# 06cpu_soc.net
KiCad netlist of a schematic drawn in Altium Designer
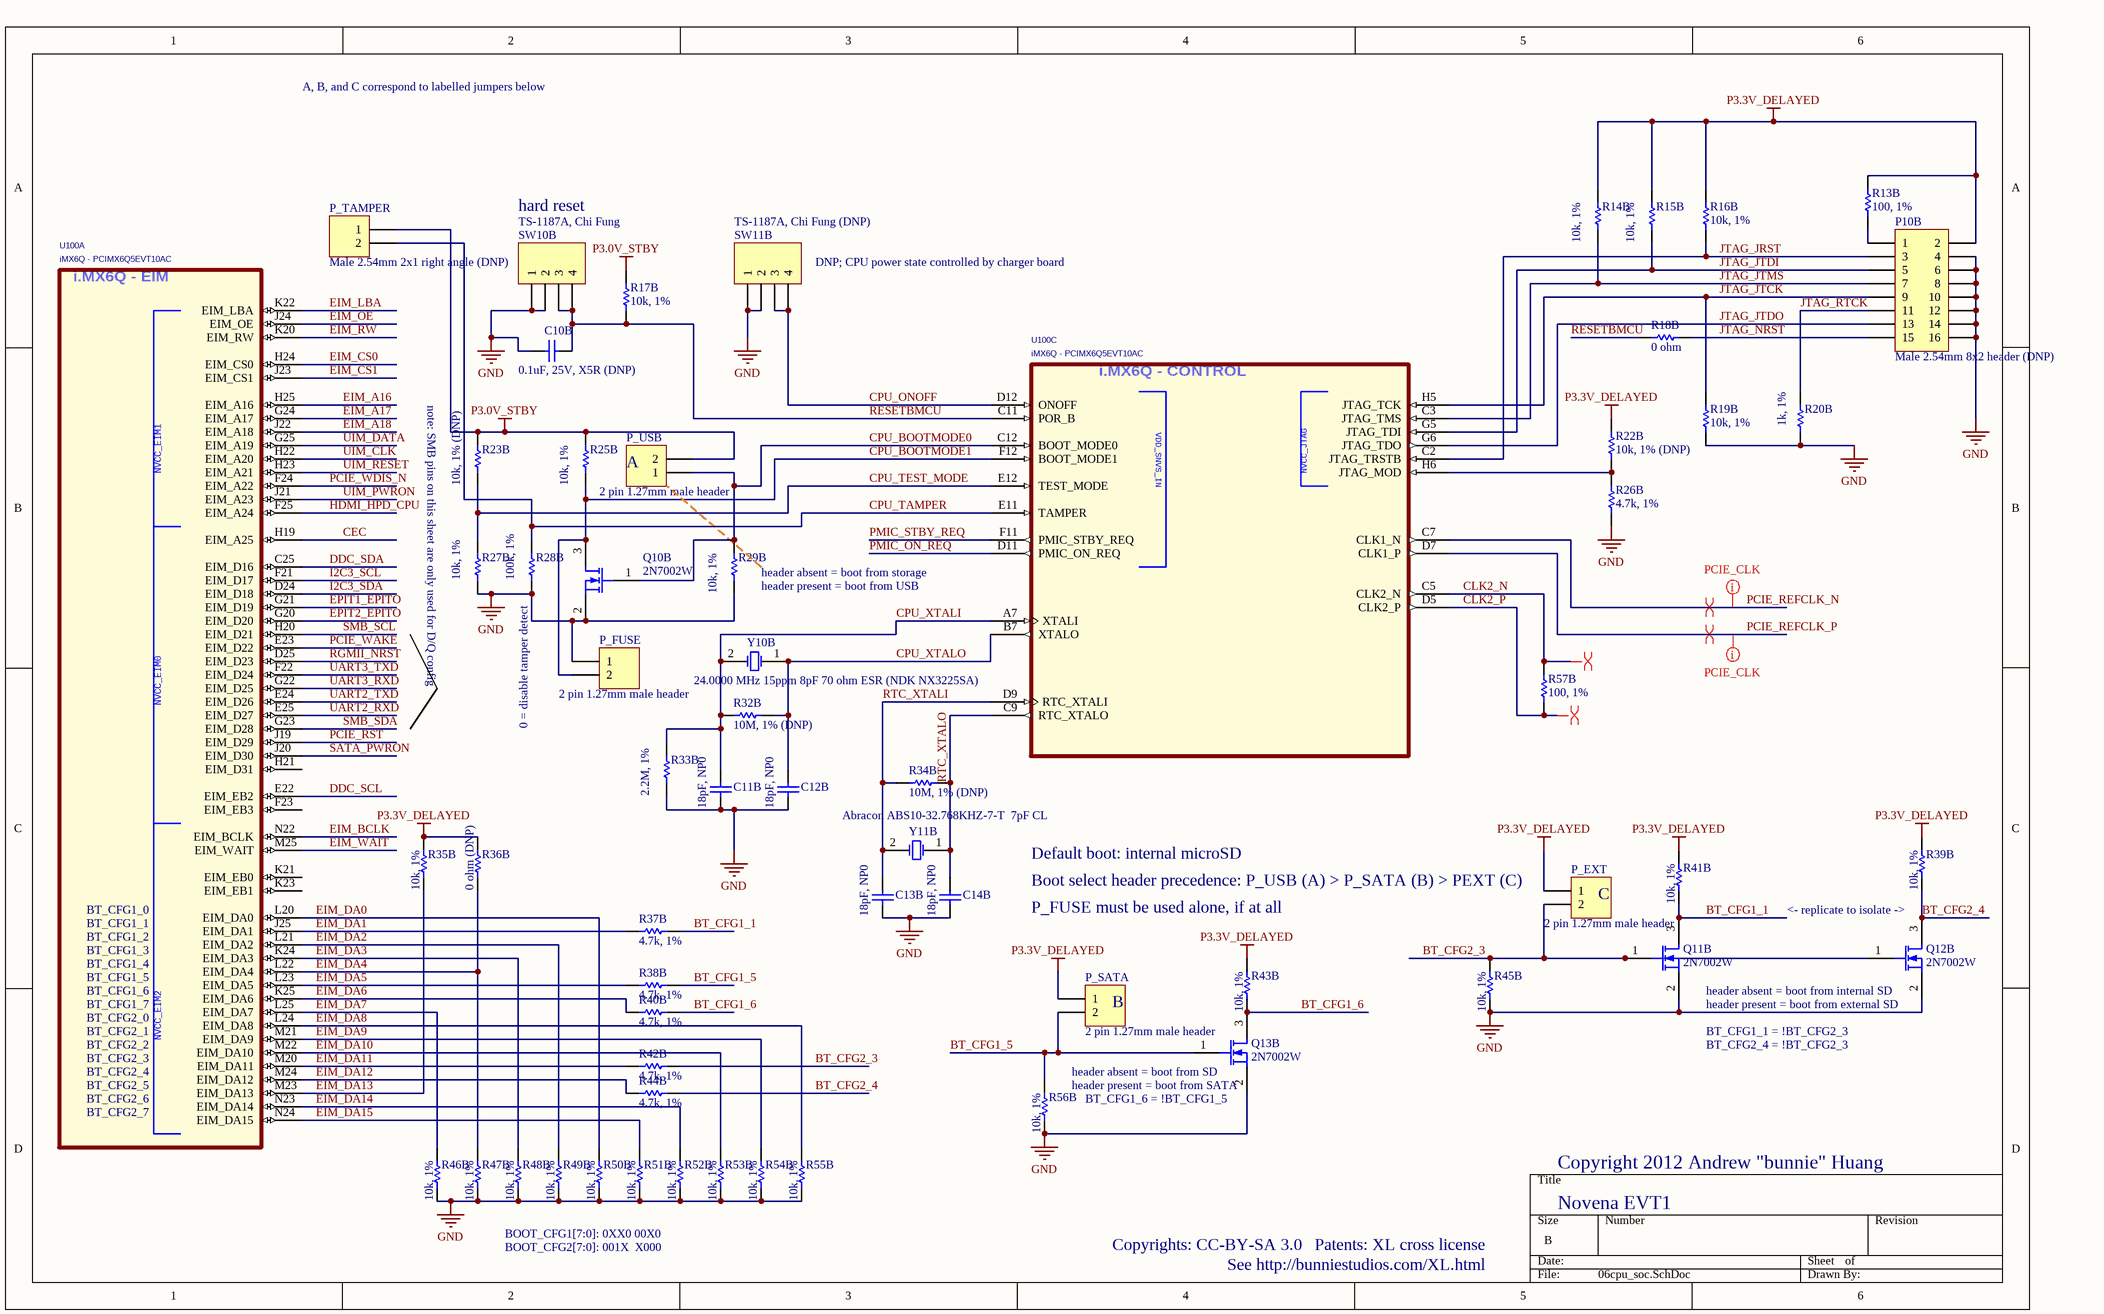
[diagram p0: 06cpu_soc.SchDoc]

(export (version "E")
  (design (tool "Eeschema 10.0.6"))
  (components
    (comp (ref "C10B")
      (value "0.1uF, 25V, X5R (DNP)")
      (footprint "CAPC1005N")
      (description "Capacitor (Semiconductor SIM Model)")
      (fields (field (name "PUBLISHER") "Altium Limited"))
      (libsource (lib "Miscellaneous Devices") (part "Cap Semi"))
    )
    (comp (ref "C11B")
      (value "18pF, NP0")
      (footprint "CAPC1005N")
      (description "Capacitor (Semiconductor SIM Model)")
      (fields (field (name "PUBLISHER") "Altium Limited"))
      (libsource (lib "Miscellaneous Devices") (part "Cap Semi"))
    )
    (comp (ref "C12B")
      (value "18pF, NP0")
      (footprint "CAPC1005N")
      (description "Capacitor (Semiconductor SIM Model)")
      (fields (field (name "PUBLISHER") "Altium Limited"))
      (libsource (lib "Miscellaneous Devices") (part "Cap Semi"))
    )
    (comp (ref "C13B")
      (value "18pF, NP0")
      (footprint "CAPC1005N")
      (description "Capacitor (Semiconductor SIM Model)")
      (fields (field (name "PUBLISHER") "Altium Limited"))
      (libsource (lib "Miscellaneous Devices") (part "Cap Semi"))
    )
    (comp (ref "C14B")
      (value "18pF, NP0")
      (footprint "CAPC1005N")
      (description "Capacitor (Semiconductor SIM Model)")
      (fields (field (name "PUBLISHER") "Altium Limited"))
      (libsource (lib "Miscellaneous Devices") (part "Cap Semi"))
    )
    (comp (ref "P10B")
      (value "Male 2.54mm 8x2 header (DNP)")
      (footprint "HDR2X8")
      (description "Header, 8-Pin, Dual row")
      (fields (field (name "PUBLISHER") "Altium Limited"))
      (libsource (lib "Miscellaneous Connectors") (part "Header 8X2"))
    )
    (comp (ref "P_EXT")
      (value "2 pin 1.27mm male header")
      (footprint "HEADER_2_1.27MM")
      (description "Header, 2-Pin")
      (fields (field (name "PUBLISHER") "Altium Limited"))
      (libsource (lib "") (part "Header 2_1"))
    )
    (comp (ref "P_FUSE")
      (value "2 pin 1.27mm male header")
      (footprint "HEADER_2_1.27MM")
      (description "Header, 2-Pin")
      (fields (field (name "PUBLISHER") "Altium Limited"))
      (libsource (lib "") (part "Header 2_1"))
    )
    (comp (ref "P_SATA")
      (value "2 pin 1.27mm male header")
      (footprint "HEADER_2_1.27MM")
      (description "Header, 2-Pin")
      (fields (field (name "PUBLISHER") "Altium Limited"))
      (libsource (lib "") (part "Header 2_1"))
    )
    (comp (ref "P_TAMPER")
      (value "Male 2.54mm 2x1 right angle (DNP)")
      (footprint "HDR1X2H")
      (description "Header, 2-Pin, Right Angle")
      (fields (field (name "PUBLISHER") "Altium Limited"))
      (libsource (lib "Miscellaneous Connectors") (part "Header 2H"))
    )
    (comp (ref "P_USB")
      (value "2 pin 1.27mm male header")
      (footprint "HEADER_2_1.27MM")
      (description "Header, 2-Pin")
      (fields (field (name "PUBLISHER") "Altium Limited"))
      (libsource (lib "Miscellaneous Connectors") (part "Header 2"))
    )
    (comp (ref "Q10B")
      (value "2N7002W")
      (footprint "SOT323-3AN")
      (description "N-Channel MOSFET")
      (fields (field (name "PUBLISHER") "Altium Limited"))
      (libsource (lib "Miscellaneous Devices") (part "MOSFET-N"))
    )
    (comp (ref "Q11B")
      (value "2N7002W")
      (footprint "SOT323-3AN")
      (description "N-Channel MOSFET")
      (fields (field (name "PUBLISHER") "Altium Limited"))
      (libsource (lib "Miscellaneous Devices") (part "MOSFET-N"))
    )
    (comp (ref "Q12B")
      (value "2N7002W")
      (footprint "SOT323-3AN")
      (description "N-Channel MOSFET")
      (fields (field (name "PUBLISHER") "Altium Limited"))
      (libsource (lib "Miscellaneous Devices") (part "MOSFET-N"))
    )
    (comp (ref "Q13B")
      (value "2N7002W")
      (footprint "SOT323-3AN")
      (description "N-Channel MOSFET")
      (fields (field (name "PUBLISHER") "Altium Limited"))
      (libsource (lib "Miscellaneous Devices") (part "MOSFET-N"))
    )
    (comp (ref "R13B")
      (value "100, 1%")
      (footprint "RESC1005N")
      (description "Resistor")
      (fields (field (name "PUBLISHER") "Altium Limited"))
      (libsource (lib "Miscellaneous Devices") (part "Res1"))
    )
    (comp (ref "R14B")
      (value "10k, 1%")
      (footprint "RESC1005N")
      (description "Resistor")
      (fields (field (name "PUBLISHER") "Altium Limited"))
      (libsource (lib "Miscellaneous Devices") (part "Res1"))
    )
    (comp (ref "R15B")
      (value "10k, 1%")
      (footprint "RESC1005N")
      (description "Resistor")
      (fields (field (name "PUBLISHER") "Altium Limited"))
      (libsource (lib "Miscellaneous Devices") (part "Res1"))
    )
    (comp (ref "R16B")
      (value "10k, 1%")
      (footprint "RESC1005N")
      (description "Resistor")
      (fields (field (name "PUBLISHER") "Altium Limited"))
      (libsource (lib "Miscellaneous Devices") (part "Res1"))
    )
    (comp (ref "R17B")
      (value "10k, 1%")
      (footprint "RESC1005N")
      (description "Resistor")
      (fields (field (name "PUBLISHER") "Altium Limited"))
      (libsource (lib "Miscellaneous Devices") (part "Res1"))
    )
    (comp (ref "R18B")
      (value "0 ohm")
      (footprint "RESC1005N")
      (description "Resistor")
      (fields (field (name "PUBLISHER") "Altium Limited"))
      (libsource (lib "Miscellaneous Devices") (part "Res1"))
    )
    (comp (ref "R19B")
      (value "10k, 1%")
      (footprint "RESC1005N")
      (description "Resistor")
      (fields (field (name "PUBLISHER") "Altium Limited"))
      (libsource (lib "Miscellaneous Devices") (part "Res1"))
    )
    (comp (ref "R20B")
      (value "1k, 1%")
      (footprint "RESC1005N")
      (description "Resistor")
      (fields (field (name "PUBLISHER") "Altium Limited"))
      (libsource (lib "Miscellaneous Devices") (part "Res1"))
    )
    (comp (ref "R22B")
      (value "10k, 1% (DNP)")
      (footprint "RESC1005N")
      (description "Resistor")
      (fields (field (name "PUBLISHER") "Altium Limited"))
      (libsource (lib "Miscellaneous Devices") (part "Res1"))
    )
    (comp (ref "R23B")
      (value "10k, 1% (DNP)")
      (footprint "RESC1005N")
      (description "Resistor")
      (fields (field (name "PUBLISHER") "Altium Limited"))
      (libsource (lib "Miscellaneous Devices") (part "Res1"))
    )
    (comp (ref "R25B")
      (value "10k, 1%")
      (footprint "RESC1005N")
      (description "Resistor")
      (fields (field (name "PUBLISHER") "Altium Limited"))
      (libsource (lib "Miscellaneous Devices") (part "Res1"))
    )
    (comp (ref "R26B")
      (value "4.7k, 1%")
      (footprint "RESC1005N")
      (description "Resistor")
      (fields (field (name "PUBLISHER") "Altium Limited"))
      (libsource (lib "Miscellaneous Devices") (part "Res1"))
    )
    (comp (ref "R27B")
      (value "10k, 1%")
      (footprint "RESC1005N")
      (description "Resistor")
      (fields (field (name "PUBLISHER") "Altium Limited"))
      (libsource (lib "Miscellaneous Devices") (part "Res1"))
    )
    (comp (ref "R28B")
      (value "100k, 1%")
      (footprint "RESC1005N")
      (description "Resistor")
      (fields (field (name "PUBLISHER") "Altium Limited"))
      (libsource (lib "Miscellaneous Devices") (part "Res1"))
    )
    (comp (ref "R29B")
      (value "10k, 1%")
      (footprint "RESC1005N")
      (description "Resistor")
      (fields (field (name "PUBLISHER") "Altium Limited"))
      (libsource (lib "Miscellaneous Devices") (part "Res1"))
    )
    (comp (ref "R32B")
      (value "10M, 1% (DNP)")
      (footprint "RESC1005N")
      (description "Resistor")
      (fields (field (name "PUBLISHER") "Altium Limited"))
      (libsource (lib "Miscellaneous Devices") (part "Res1"))
    )
    (comp (ref "R33B")
      (value "2.2M, 1%")
      (footprint "RESC1005N")
      (description "Resistor")
      (fields (field (name "PUBLISHER") "Altium Limited"))
      (libsource (lib "Miscellaneous Devices") (part "Res1"))
    )
    (comp (ref "R34B")
      (value "10M, 1% (DNP)")
      (footprint "RESC1005N")
      (description "Resistor")
      (fields (field (name "PUBLISHER") "Altium Limited"))
      (libsource (lib "Miscellaneous Devices") (part "Res1"))
    )
    (comp (ref "R35B")
      (value "10k, 1%")
      (footprint "RESC1005N")
      (description "Resistor")
      (fields (field (name "PUBLISHER") "Altium Limited"))
      (libsource (lib "Miscellaneous Devices") (part "Res1"))
    )
    (comp (ref "R36B")
      (value "0 ohm (DNP)")
      (footprint "RESC1005N")
      (description "Resistor")
      (fields (field (name "PUBLISHER") "Altium Limited"))
      (libsource (lib "Miscellaneous Devices") (part "Res1"))
    )
    (comp (ref "R37B")
      (value "4.7k, 1%")
      (footprint "RESC1005N")
      (description "Resistor")
      (fields (field (name "PUBLISHER") "Altium Limited"))
      (libsource (lib "Miscellaneous Devices") (part "Res1"))
    )
    (comp (ref "R38B")
      (value "4.7k, 1%")
      (footprint "RESC1005N")
      (description "Resistor")
      (fields (field (name "PUBLISHER") "Altium Limited"))
      (libsource (lib "Miscellaneous Devices") (part "Res1"))
    )
    (comp (ref "R39B")
      (value "10k, 1%")
      (footprint "RESC1005N")
      (description "Resistor")
      (fields (field (name "PUBLISHER") "Altium Limited"))
      (libsource (lib "Miscellaneous Devices") (part "Res1"))
    )
    (comp (ref "R40B")
      (value "4.7k, 1%")
      (footprint "RESC1005N")
      (description "Resistor")
      (fields (field (name "PUBLISHER") "Altium Limited"))
      (libsource (lib "Miscellaneous Devices") (part "Res1"))
    )
    (comp (ref "R41B")
      (value "10k, 1%")
      (footprint "RESC1005N")
      (description "Resistor")
      (fields (field (name "PUBLISHER") "Altium Limited"))
      (libsource (lib "Miscellaneous Devices") (part "Res1"))
    )
    (comp (ref "R42B")
      (value "4.7k, 1%")
      (footprint "RESC1005N")
      (description "Resistor")
      (fields (field (name "PUBLISHER") "Altium Limited"))
      (libsource (lib "Miscellaneous Devices") (part "Res1"))
    )
    (comp (ref "R43B")
      (value "10k, 1%")
      (footprint "RESC1005N")
      (description "Resistor")
      (fields (field (name "PUBLISHER") "Altium Limited"))
      (libsource (lib "Miscellaneous Devices") (part "Res1"))
    )
    (comp (ref "R44B")
      (value "4.7k, 1%")
      (footprint "RESC1005N")
      (description "Resistor")
      (fields (field (name "PUBLISHER") "Altium Limited"))
      (libsource (lib "Miscellaneous Devices") (part "Res1"))
    )
    (comp (ref "R45B")
      (value "10k, 1%")
      (footprint "RESC1005N")
      (description "Resistor")
      (fields (field (name "PUBLISHER") "Altium Limited"))
      (libsource (lib "Miscellaneous Devices") (part "Res1"))
    )
    (comp (ref "R46B")
      (value "10k, 1%")
      (footprint "RESC1005N")
      (description "Resistor")
      (fields (field (name "PUBLISHER") "Altium Limited"))
      (libsource (lib "Miscellaneous Devices") (part "Res1"))
    )
    (comp (ref "R47B")
      (value "10k, 1%")
      (footprint "RESC1005N")
      (description "Resistor")
      (fields (field (name "PUBLISHER") "Altium Limited"))
      (libsource (lib "Miscellaneous Devices") (part "Res1"))
    )
    (comp (ref "R48B")
      (value "10k, 1%")
      (footprint "RESC1005N")
      (description "Resistor")
      (fields (field (name "PUBLISHER") "Altium Limited"))
      (libsource (lib "Miscellaneous Devices") (part "Res1"))
    )
    (comp (ref "R49B")
      (value "10k, 1%")
      (footprint "RESC1005N")
      (description "Resistor")
      (fields (field (name "PUBLISHER") "Altium Limited"))
      (libsource (lib "Miscellaneous Devices") (part "Res1"))
    )
    (comp (ref "R50B")
      (value "10k, 1%")
      (footprint "RESC1005N")
      (description "Resistor")
      (fields (field (name "PUBLISHER") "Altium Limited"))
      (libsource (lib "Miscellaneous Devices") (part "Res1"))
    )
    (comp (ref "R51B")
      (value "10k, 1%")
      (footprint "RESC1005N")
      (description "Resistor")
      (fields (field (name "PUBLISHER") "Altium Limited"))
      (libsource (lib "Miscellaneous Devices") (part "Res1"))
    )
    (comp (ref "R52B")
      (value "10k, 1%")
      (footprint "RESC1005N")
      (description "Resistor")
      (fields (field (name "PUBLISHER") "Altium Limited"))
      (libsource (lib "Miscellaneous Devices") (part "Res1"))
    )
    (comp (ref "R53B")
      (value "10k, 1%")
      (footprint "RESC1005N")
      (description "Resistor")
      (fields (field (name "PUBLISHER") "Altium Limited"))
      (libsource (lib "Miscellaneous Devices") (part "Res1"))
    )
    (comp (ref "R54B")
      (value "10k, 1%")
      (footprint "RESC1005N")
      (description "Resistor")
      (fields (field (name "PUBLISHER") "Altium Limited"))
      (libsource (lib "Miscellaneous Devices") (part "Res1"))
    )
    (comp (ref "R55B")
      (value "10k, 1%")
      (footprint "RESC1005N")
      (description "Resistor")
      (fields (field (name "PUBLISHER") "Altium Limited"))
      (libsource (lib "Miscellaneous Devices") (part "Res1"))
    )
    (comp (ref "R56B")
      (value "10k, 1%")
      (footprint "RESC1005N")
      (description "Resistor")
      (fields (field (name "PUBLISHER") "Altium Limited"))
      (libsource (lib "Miscellaneous Devices") (part "Res1"))
    )
    (comp (ref "R57B")
      (value "100, 1%")
      (footprint "RESC1005N")
      (description "Resistor")
      (fields (field (name "PUBLISHER") "Altium Limited"))
      (libsource (lib "Miscellaneous Devices") (part "Res1"))
    )
    (comp (ref "SW10B")
      (value "TS-1187A, Chi Fung")
      (footprint "SWITCH_TS-1187A")
      (description "Chi Fung TS-1187A")
      (fields (field (name "PUBLISHER") "Altium Limited"))
      (libsource (lib "Miscellaneous Connectors") (part "Header 4"))
    )
    (comp (ref "SW11B")
      (value "TS-1187A, Chi Fung (DNP)")
      (footprint "SWITCH_TS-1187A")
      (description "Chi Fung TS-1187A")
      (fields (field (name "PUBLISHER") "Altium Limited"))
      (libsource (lib "Miscellaneous Connectors") (part "Header 4"))
    )
    (comp (ref "U100")
      (value "iMX6Q - PCIMX6Q5EVT10AC")
      (description "PLACEHOLDER FOR FREESCALE PART NUMBER PMCIMX6Q6VV1A.")
      (libsource (lib "*") (part "PCIMX6Q6VV1A"))
    )
    (comp (ref "Y10B")
      (value "24.0000 MHz 15ppm 8pF 70 ohm ESR (NDK NX3225SA)")
      (footprint "NDK_NX3225SA")
      (description "Crystal Oscillator")
      (fields (field (name "PUBLISHER") "Altium Limited"))
      (libsource (lib "Miscellaneous Devices") (part "XTAL"))
    )
    (comp (ref "Y11B")
      (value "Abracon ABS10-32.768KHZ-7-T  7pF CL")
      (footprint "ABS10-32.768KHZ")
      (description "Crystal Oscillator")
      (fields (field (name "PUBLISHER") "Altium Limited"))
      (libsource (lib "Miscellaneous Devices") (part "XTAL"))
    )
  )
  (nets
    (net (code "1") (name "/BT_CFG1_1") (class "Default")
      (node (ref "Q11B") (pin "3") (pinfunction "D_3") (pintype "passive"))
      (node (ref "R37B") (pin "2") (pinfunction "2_2") (pintype "passive"))
      (node (ref "R41B") (pin "2") (pinfunction "2_2") (pintype "passive"))
    )
    (net (code "2") (name "/BT_CFG1_5") (class "Default")
      (node (ref "P_SATA") (pin "2") (pinfunction "2_2") (pintype "passive"))
      (node (ref "Q13B") (pin "1") (pinfunction "G_1") (pintype "passive"))
      (node (ref "R38B") (pin "2") (pinfunction "2_2") (pintype "passive"))
      (node (ref "R56B") (pin "1") (pinfunction "1_1") (pintype "passive"))
    )
    (net (code "3") (name "/BT_CFG1_6") (class "Default")
      (node (ref "Q13B") (pin "3") (pinfunction "D_3") (pintype "passive"))
      (node (ref "R40B") (pin "2") (pinfunction "2_2") (pintype "passive"))
      (node (ref "R43B") (pin "2") (pinfunction "2_2") (pintype "passive"))
    )
    (net (code "4") (name "/BT_CFG2_3") (class "Default")
      (node (ref "P_EXT") (pin "2") (pinfunction "2_2") (pintype "passive"))
      (node (ref "Q11B") (pin "1") (pinfunction "G_1") (pintype "passive"))
      (node (ref "Q12B") (pin "1") (pinfunction "G_1") (pintype "passive"))
      (node (ref "R42B") (pin "2") (pinfunction "2_2") (pintype "passive"))
      (node (ref "R45B") (pin "1") (pinfunction "1_1") (pintype "passive"))
    )
    (net (code "5") (name "/BT_CFG2_4") (class "Default")
      (node (ref "Q12B") (pin "3") (pinfunction "D_3") (pintype "passive"))
      (node (ref "R39B") (pin "2") (pinfunction "2_2") (pintype "passive"))
      (node (ref "R44B") (pin "2") (pinfunction "2_2") (pintype "passive"))
    )
    (net (code "6") (name "/CEC") (class "Default")
      (node (ref "U100") (pin "H19") (pinfunction "EIM_A25_H19") (pintype "bidirectional"))
    )
    (net (code "7") (name "/CLK2_N") (class "Default")
      (node (ref "R57B") (pin "2") (pinfunction "2_2") (pintype "passive"))
      (node (ref "U100") (pin "C5") (pinfunction "CLK2_N_C5") (pintype "output"))
    )
    (net (code "8") (name "/CLK2_P") (class "Default")
      (node (ref "R57B") (pin "1") (pinfunction "1_1") (pintype "passive"))
      (node (ref "U100") (pin "D5") (pinfunction "CLK2_P_D5") (pintype "output"))
    )
    (net (code "9") (name "/CPU_BOOTMODE0") (class "Default")
      (node (ref "P_USB") (pin "1") (pinfunction "1_1") (pintype "passive"))
      (node (ref "Q10B") (pin "1") (pinfunction "G_1") (pintype "passive"))
      (node (ref "R29B") (pin "2") (pinfunction "2_2") (pintype "passive"))
      (node (ref "U100") (pin "C12") (pinfunction "BOOT_MODE0_C12") (pintype "input"))
    )
    (net (code "10") (name "/CPU_BOOTMODE1") (class "Default")
      (node (ref "P_FUSE") (pin "2") (pinfunction "2_2") (pintype "passive"))
      (node (ref "Q10B") (pin "3") (pinfunction "D_3") (pintype "passive"))
      (node (ref "R25B") (pin "1") (pinfunction "1_1") (pintype "passive"))
      (node (ref "U100") (pin "F12") (pinfunction "BOOT_MODE1_F12") (pintype "input"))
    )
    (net (code "11") (name "/CPU_ONOFF") (class "Default")
      (node (ref "SW11B") (pin "3") (pinfunction "3_3") (pintype "passive"))
      (node (ref "SW11B") (pin "4") (pinfunction "4_4") (pintype "passive"))
      (node (ref "U100") (pin "D12") (pinfunction "ONOFF_D12") (pintype "input"))
    )
    (net (code "12") (name "/CPU_TAMPER") (class "Default")
      (node (ref "P_TAMPER") (pin "2") (pinfunction "2_2") (pintype "passive"))
      (node (ref "R28B") (pin "2") (pinfunction "2_2") (pintype "passive"))
      (node (ref "U100") (pin "E11") (pinfunction "TAMPER_E11") (pintype "input"))
    )
    (net (code "13") (name "/CPU_TEST_MODE") (class "Default")
      (node (ref "R23B") (pin "1") (pinfunction "1_1") (pintype "passive"))
      (node (ref "R27B") (pin "2") (pinfunction "2_2") (pintype "passive"))
      (node (ref "U100") (pin "E12") (pinfunction "TEST_MODE_E12") (pintype "input"))
    )
    (net (code "14") (name "/CPU_XTALI") (class "Default")
      (node (ref "C11B") (pin "1") (pinfunction "1_1") (pintype "passive"))
      (node (ref "R32B") (pin "1") (pinfunction "1_1") (pintype "passive"))
      (node (ref "R33B") (pin "1") (pinfunction "1_1") (pintype "passive"))
      (node (ref "U100") (pin "A7") (pinfunction "XTALI_A7") (pintype "input"))
      (node (ref "Y10B") (pin "2") (pinfunction "OSC2_2") (pintype "passive"))
    )
    (net (code "15") (name "/CPU_XTALO") (class "Default")
      (node (ref "C12B") (pin "1") (pinfunction "1_1") (pintype "passive"))
      (node (ref "R32B") (pin "2") (pinfunction "2_2") (pintype "passive"))
      (node (ref "U100") (pin "B7") (pinfunction "XTALO_B7") (pintype "output"))
      (node (ref "Y10B") (pin "1") (pinfunction "OSC1_1") (pintype "passive"))
    )
    (net (code "16") (name "/DDC_SCL") (class "Default")
      (node (ref "U100") (pin "E22") (pinfunction "EIM_EB2_E22") (pintype "bidirectional"))
    )
    (net (code "17") (name "/DDC_SDA") (class "Default")
      (node (ref "U100") (pin "C25") (pinfunction "EIM_D16_C25") (pintype "bidirectional"))
    )
    (net (code "18") (name "/EIM_A16") (class "Default")
      (node (ref "U100") (pin "H25") (pinfunction "EIM_A16_H25") (pintype "bidirectional"))
    )
    (net (code "19") (name "/EIM_A17") (class "Default")
      (node (ref "U100") (pin "G24") (pinfunction "EIM_A17_G24") (pintype "bidirectional"))
    )
    (net (code "20") (name "/EIM_A18") (class "Default")
      (node (ref "U100") (pin "J22") (pinfunction "EIM_A18_J22") (pintype "bidirectional"))
    )
    (net (code "21") (name "/EIM_BCLK") (class "Default")
      (node (ref "U100") (pin "N22") (pinfunction "EIM_BCLK_N22") (pintype "bidirectional"))
    )
    (net (code "22") (name "/EIM_CS0") (class "Default")
      (node (ref "U100") (pin "H24") (pinfunction "EIM_CS0_H24") (pintype "bidirectional"))
    )
    (net (code "23") (name "/EIM_CS1") (class "Default")
      (node (ref "U100") (pin "J23") (pinfunction "EIM_CS1_J23") (pintype "bidirectional"))
    )
    (net (code "24") (name "/EIM_DA0") (class "Default")
      (node (ref "R50B") (pin "1") (pinfunction "1_1") (pintype "passive"))
      (node (ref "U100") (pin "L20") (pinfunction "EIM_DA0_L20") (pintype "bidirectional"))
    )
    (net (code "25") (name "/EIM_DA1") (class "Default")
      (node (ref "R37B") (pin "1") (pinfunction "1_1") (pintype "passive"))
      (node (ref "U100") (pin "J25") (pinfunction "EIM_DA1_J25") (pintype "bidirectional"))
    )
    (net (code "26") (name "/EIM_DA2") (class "Default")
      (node (ref "R49B") (pin "1") (pinfunction "1_1") (pintype "passive"))
      (node (ref "U100") (pin "L21") (pinfunction "EIM_DA2_L21") (pintype "bidirectional"))
    )
    (net (code "27") (name "/EIM_DA3") (class "Default")
      (node (ref "R48B") (pin "1") (pinfunction "1_1") (pintype "passive"))
      (node (ref "U100") (pin "K24") (pinfunction "EIM_DA3_K24") (pintype "bidirectional"))
    )
    (net (code "28") (name "/EIM_DA4") (class "Default")
      (node (ref "R36B") (pin "2") (pinfunction "2_2") (pintype "passive"))
      (node (ref "R47B") (pin "1") (pinfunction "1_1") (pintype "passive"))
      (node (ref "U100") (pin "L22") (pinfunction "EIM_DA4_L22") (pintype "bidirectional"))
    )
    (net (code "29") (name "/EIM_DA5") (class "Default")
      (node (ref "R38B") (pin "1") (pinfunction "1_1") (pintype "passive"))
      (node (ref "U100") (pin "L23") (pinfunction "EIM_DA5_L23") (pintype "bidirectional"))
    )
    (net (code "30") (name "/EIM_DA6") (class "Default")
      (node (ref "R40B") (pin "1") (pinfunction "1_1") (pintype "passive"))
      (node (ref "U100") (pin "K25") (pinfunction "EIM_DA6_K25") (pintype "bidirectional"))
    )
    (net (code "31") (name "/EIM_DA7") (class "Default")
      (node (ref "R46B") (pin "1") (pinfunction "1_1") (pintype "passive"))
      (node (ref "U100") (pin "L25") (pinfunction "EIM_DA7_L25") (pintype "bidirectional"))
    )
    (net (code "32") (name "/EIM_DA8") (class "Default")
      (node (ref "R55B") (pin "1") (pinfunction "1_1") (pintype "passive"))
      (node (ref "U100") (pin "L24") (pinfunction "EIM_DA8_L24") (pintype "bidirectional"))
    )
    (net (code "33") (name "/EIM_DA9") (class "Default")
      (node (ref "R54B") (pin "1") (pinfunction "1_1") (pintype "passive"))
      (node (ref "U100") (pin "M21") (pinfunction "EIM_DA9_M21") (pintype "bidirectional"))
    )
    (net (code "34") (name "/EIM_DA10") (class "Default")
      (node (ref "R53B") (pin "1") (pinfunction "1_1") (pintype "passive"))
      (node (ref "U100") (pin "M22") (pinfunction "EIM_DA10_M22") (pintype "bidirectional"))
    )
    (net (code "35") (name "/EIM_DA11") (class "Default")
      (node (ref "R42B") (pin "1") (pinfunction "1_1") (pintype "passive"))
      (node (ref "U100") (pin "M20") (pinfunction "EIM_DA11_M20") (pintype "bidirectional"))
    )
    (net (code "36") (name "/EIM_DA12") (class "Default")
      (node (ref "R44B") (pin "1") (pinfunction "1_1") (pintype "passive"))
      (node (ref "U100") (pin "M24") (pinfunction "EIM_DA12_M24") (pintype "bidirectional"))
    )
    (net (code "37") (name "/EIM_DA13") (class "Default")
      (node (ref "R35B") (pin "2") (pinfunction "2_2") (pintype "passive"))
      (node (ref "U100") (pin "M23") (pinfunction "EIM_DA13_M23") (pintype "bidirectional"))
    )
    (net (code "38") (name "/EIM_DA14") (class "Default")
      (node (ref "R52B") (pin "1") (pinfunction "1_1") (pintype "passive"))
      (node (ref "U100") (pin "N23") (pinfunction "EIM_DA14_N23") (pintype "bidirectional"))
    )
    (net (code "39") (name "/EIM_DA15") (class "Default")
      (node (ref "R51B") (pin "1") (pinfunction "1_1") (pintype "passive"))
      (node (ref "U100") (pin "N24") (pinfunction "EIM_DA15_N24") (pintype "bidirectional"))
    )
    (net (code "40") (name "/EIM_LBA") (class "Default")
      (node (ref "U100") (pin "K22") (pinfunction "EIM_LBA_K22") (pintype "bidirectional"))
    )
    (net (code "41") (name "/EIM_OE") (class "Default")
      (node (ref "U100") (pin "J24") (pinfunction "EIM_OE_J24") (pintype "bidirectional"))
    )
    (net (code "42") (name "/EIM_RW") (class "Default")
      (node (ref "U100") (pin "K20") (pinfunction "EIM_RW_K20") (pintype "bidirectional"))
    )
    (net (code "43") (name "/EIM_WAIT") (class "Default")
      (node (ref "U100") (pin "M25") (pinfunction "EIM_WAIT_M25") (pintype "bidirectional"))
    )
    (net (code "44") (name "/EPIT1_EPITO") (class "Default")
      (node (ref "U100") (pin "G21") (pinfunction "EIM_D19_G21") (pintype "bidirectional"))
    )
    (net (code "45") (name "/EPIT2_EPITO") (class "Default")
      (node (ref "U100") (pin "G20") (pinfunction "EIM_D20_G20") (pintype "bidirectional"))
    )
    (net (code "46") (name "/HDMI_HPD_CPU") (class "Default")
      (node (ref "U100") (pin "F25") (pinfunction "EIM_A24_F25") (pintype "bidirectional"))
    )
    (net (code "47") (name "/I2C3_SCL") (class "Default")
      (node (ref "U100") (pin "F21") (pinfunction "EIM_D17_F21") (pintype "bidirectional"))
    )
    (net (code "48") (name "/I2C3_SDA") (class "Default")
      (node (ref "U100") (pin "D24") (pinfunction "EIM_D18_D24") (pintype "bidirectional"))
    )
    (net (code "49") (name "/JTAG_JRST") (class "Default")
      (node (ref "P10B") (pin "3") (pinfunction "3_3") (pintype "passive"))
      (node (ref "R16B") (pin "1") (pinfunction "1_1") (pintype "passive"))
      (node (ref "U100") (pin "C2") (pinfunction "JTAG_TRSTB_C2") (pintype "input"))
    )
    (net (code "50") (name "/JTAG_JTCK") (class "Default")
      (node (ref "P10B") (pin "9") (pinfunction "9_9") (pintype "passive"))
      (node (ref "R19B") (pin "2") (pinfunction "2_2") (pintype "passive"))
      (node (ref "U100") (pin "H5") (pinfunction "JTAG_TCK_H5") (pintype "input"))
    )
    (net (code "51") (name "/JTAG_JTDI") (class "Default")
      (node (ref "P10B") (pin "5") (pinfunction "5_5") (pintype "passive"))
      (node (ref "R15B") (pin "1") (pinfunction "1_1") (pintype "passive"))
      (node (ref "U100") (pin "G5") (pinfunction "JTAG_TDI_G5") (pintype "input"))
    )
    (net (code "52") (name "/JTAG_JTDO") (class "Default")
      (node (ref "P10B") (pin "13") (pinfunction "13_13") (pintype "passive"))
      (node (ref "U100") (pin "G6") (pinfunction "JTAG_TDO_G6") (pintype "output"))
    )
    (net (code "53") (name "/JTAG_JTMS") (class "Default")
      (node (ref "P10B") (pin "7") (pinfunction "7_7") (pintype "passive"))
      (node (ref "R14B") (pin "1") (pinfunction "1_1") (pintype "passive"))
      (node (ref "U100") (pin "C3") (pinfunction "JTAG_TMS_C3") (pintype "input"))
    )
    (net (code "54") (name "/JTAG_NRST") (class "Default")
      (node (ref "P10B") (pin "15") (pinfunction "15_15") (pintype "passive"))
      (node (ref "R18B") (pin "1") (pinfunction "1_1") (pintype "passive"))
    )
    (net (code "55") (name "/JTAG_RTCK") (class "Default")
      (node (ref "P10B") (pin "11") (pinfunction "11_11") (pintype "passive"))
      (node (ref "R20B") (pin "2") (pinfunction "2_2") (pintype "passive"))
    )
    (net (code "56") (name "/PCIE_REFCLK_N") (class "Default")
      (node (ref "U100") (pin "C7") (pinfunction "CLK1_N_C7") (pintype "output"))
    )
    (net (code "57") (name "/PCIE_REFCLK_P") (class "Default")
      (node (ref "U100") (pin "D7") (pinfunction "CLK1_P_D7") (pintype "output"))
    )
    (net (code "58") (name "/PCIE_RST") (class "Default")
      (node (ref "U100") (pin "J19") (pinfunction "EIM_D29_J19") (pintype "bidirectional"))
    )
    (net (code "59") (name "/PCIE_WAKE") (class "Default")
      (node (ref "U100") (pin "E23") (pinfunction "EIM_D22_E23") (pintype "bidirectional"))
    )
    (net (code "60") (name "/PCIE_WDIS_N") (class "Default")
      (node (ref "U100") (pin "F24") (pinfunction "EIM_A22_F24") (pintype "bidirectional"))
    )
    (net (code "61") (name "/PMIC_ON_REQ") (class "Default")
      (node (ref "U100") (pin "D11") (pinfunction "PMIC_ON_REQ_D11") (pintype "output"))
    )
    (net (code "62") (name "/PMIC_STBY_REQ") (class "Default")
      (node (ref "U100") (pin "F11") (pinfunction "PMIC_STBY_REQ_F11") (pintype "output"))
    )
    (net (code "63") (name "/RESETBMCU") (class "Default")
      (node (ref "C10B") (pin "1") (pinfunction "1_1") (pintype "passive"))
      (node (ref "R17B") (pin "1") (pinfunction "1_1") (pintype "passive"))
      (node (ref "R18B") (pin "2") (pinfunction "2_2") (pintype "passive"))
      (node (ref "SW10B") (pin "3") (pinfunction "3_3") (pintype "passive"))
      (node (ref "SW10B") (pin "4") (pinfunction "4_4") (pintype "passive"))
      (node (ref "U100") (pin "C11") (pinfunction "POR_B_C11") (pintype "input"))
    )
    (net (code "64") (name "/RGMII_NRST") (class "Default")
      (node (ref "U100") (pin "D25") (pinfunction "EIM_D23_D25") (pintype "bidirectional"))
    )
    (net (code "65") (name "/RTC_XTALI") (class "Default")
      (node (ref "C13B") (pin "1") (pinfunction "1_1") (pintype "passive"))
      (node (ref "R34B") (pin "1") (pinfunction "1_1") (pintype "passive"))
      (node (ref "U100") (pin "D9") (pinfunction "RTC_XTALI_D9") (pintype "input"))
      (node (ref "Y11B") (pin "2") (pinfunction "OSC2_2") (pintype "passive"))
    )
    (net (code "66") (name "/RTC_XTALO") (class "Default")
      (node (ref "C14B") (pin "1") (pinfunction "1_1") (pintype "passive"))
      (node (ref "R34B") (pin "2") (pinfunction "2_2") (pintype "passive"))
      (node (ref "U100") (pin "C9") (pinfunction "RTC_XTALO_C9") (pintype "output"))
      (node (ref "Y11B") (pin "1") (pinfunction "OSC1_1") (pintype "passive"))
    )
    (net (code "67") (name "/SATA_PWRON") (class "Default")
      (node (ref "U100") (pin "J20") (pinfunction "EIM_D30_J20") (pintype "bidirectional"))
    )
    (net (code "68") (name "/SMB_SCL") (class "Default")
      (node (ref "U100") (pin "H20") (pinfunction "EIM_D21_H20") (pintype "bidirectional"))
    )
    (net (code "69") (name "/SMB_SDA") (class "Default")
      (node (ref "U100") (pin "G23") (pinfunction "EIM_D28_G23") (pintype "bidirectional"))
    )
    (net (code "70") (name "/UART2_RXD") (class "Default")
      (node (ref "U100") (pin "E25") (pinfunction "EIM_D27_E25") (pintype "bidirectional"))
    )
    (net (code "71") (name "/UART2_TXD") (class "Default")
      (node (ref "U100") (pin "E24") (pinfunction "EIM_D26_E24") (pintype "bidirectional"))
    )
    (net (code "72") (name "/UART3_RXD") (class "Default")
      (node (ref "U100") (pin "G22") (pinfunction "EIM_D25_G22") (pintype "bidirectional"))
    )
    (net (code "73") (name "/UART3_TXD") (class "Default")
      (node (ref "U100") (pin "F22") (pinfunction "EIM_D24_F22") (pintype "bidirectional"))
    )
    (net (code "74") (name "/UIM_CLK") (class "Default")
      (node (ref "U100") (pin "H22") (pinfunction "EIM_A20_H22") (pintype "bidirectional"))
    )
    (net (code "75") (name "/UIM_DATA") (class "Default")
      (node (ref "U100") (pin "G25") (pinfunction "EIM_A19_G25") (pintype "bidirectional"))
    )
    (net (code "76") (name "/UIM_PWRON") (class "Default")
      (node (ref "U100") (pin "J21") (pinfunction "EIM_A23_J21") (pintype "bidirectional"))
    )
    (net (code "77") (name "/UIM_RESET") (class "Default")
      (node (ref "U100") (pin "H23") (pinfunction "EIM_A21_H23") (pintype "bidirectional"))
    )
    (net (code "78") (name "GND") (class "Default")
      (node (ref "C10B") (pin "2") (pinfunction "2_2") (pintype "passive"))
      (node (ref "C11B") (pin "2") (pinfunction "2_2") (pintype "passive"))
      (node (ref "C12B") (pin "2") (pinfunction "2_2") (pintype "passive"))
      (node (ref "C13B") (pin "2") (pinfunction "2_2") (pintype "passive"))
      (node (ref "C14B") (pin "2") (pinfunction "2_2") (pintype "passive"))
      (node (ref "P10B") (pin "10") (pinfunction "10_10") (pintype "passive"))
      (node (ref "P10B") (pin "12") (pinfunction "12_12") (pintype "passive"))
      (node (ref "P10B") (pin "14") (pinfunction "14_14") (pintype "passive"))
      (node (ref "P10B") (pin "16") (pinfunction "16_16") (pintype "passive"))
      (node (ref "P10B") (pin "4") (pinfunction "4_4") (pintype "passive"))
      (node (ref "P10B") (pin "6") (pinfunction "6_6") (pintype "passive"))
      (node (ref "P10B") (pin "8") (pinfunction "8_8") (pintype "passive"))
      (node (ref "P_FUSE") (pin "1") (pinfunction "1_1") (pintype "passive"))
      (node (ref "Q10B") (pin "2") (pinfunction "S_2") (pintype "passive"))
      (node (ref "Q11B") (pin "2") (pinfunction "S_2") (pintype "passive"))
      (node (ref "Q12B") (pin "2") (pinfunction "S_2") (pintype "passive"))
      (node (ref "Q13B") (pin "2") (pinfunction "S_2") (pintype "passive"))
      (node (ref "R19B") (pin "1") (pinfunction "1_1") (pintype "passive"))
      (node (ref "R20B") (pin "1") (pinfunction "1_1") (pintype "passive"))
      (node (ref "R26B") (pin "1") (pinfunction "1_1") (pintype "passive"))
      (node (ref "R27B") (pin "1") (pinfunction "1_1") (pintype "passive"))
      (node (ref "R28B") (pin "1") (pinfunction "1_1") (pintype "passive"))
      (node (ref "R29B") (pin "1") (pinfunction "1_1") (pintype "passive"))
      (node (ref "R33B") (pin "2") (pinfunction "2_2") (pintype "passive"))
      (node (ref "R45B") (pin "2") (pinfunction "2_2") (pintype "passive"))
      (node (ref "R46B") (pin "2") (pinfunction "2_2") (pintype "passive"))
      (node (ref "R47B") (pin "2") (pinfunction "2_2") (pintype "passive"))
      (node (ref "R48B") (pin "2") (pinfunction "2_2") (pintype "passive"))
      (node (ref "R49B") (pin "2") (pinfunction "2_2") (pintype "passive"))
      (node (ref "R50B") (pin "2") (pinfunction "2_2") (pintype "passive"))
      (node (ref "R51B") (pin "2") (pinfunction "2_2") (pintype "passive"))
      (node (ref "R52B") (pin "2") (pinfunction "2_2") (pintype "passive"))
      (node (ref "R53B") (pin "2") (pinfunction "2_2") (pintype "passive"))
      (node (ref "R54B") (pin "2") (pinfunction "2_2") (pintype "passive"))
      (node (ref "R55B") (pin "2") (pinfunction "2_2") (pintype "passive"))
      (node (ref "R56B") (pin "2") (pinfunction "2_2") (pintype "passive"))
      (node (ref "SW10B") (pin "1") (pinfunction "1_1") (pintype "passive"))
      (node (ref "SW10B") (pin "2") (pinfunction "2_2") (pintype "passive"))
      (node (ref "SW11B") (pin "1") (pinfunction "1_1") (pintype "passive"))
      (node (ref "SW11B") (pin "2") (pinfunction "2_2") (pintype "passive"))
    )
    (net (code "79") (name "Net-(P10B-Pad1)") (class "Default")
      (node (ref "P10B") (pin "1") (pinfunction "1_1") (pintype "passive"))
      (node (ref "R13B") (pin "1") (pinfunction "1_1") (pintype "passive"))
    )
    (net (code "80") (name "Net-(U100C-JTAG_MOD)") (class "Default")
      (node (ref "R22B") (pin "1") (pinfunction "1_1") (pintype "passive"))
      (node (ref "R26B") (pin "2") (pinfunction "2_2") (pintype "passive"))
      (node (ref "U100") (pin "H6") (pinfunction "JTAG_MOD_H6") (pintype "input"))
    )
    (net (code "81") (name "P3.0V_STBY") (class "Default")
      (node (ref "P_TAMPER") (pin "1") (pinfunction "1_1") (pintype "passive"))
      (node (ref "P_USB") (pin "2") (pinfunction "2_2") (pintype "passive"))
      (node (ref "R17B") (pin "2") (pinfunction "2_2") (pintype "passive"))
      (node (ref "R23B") (pin "2") (pinfunction "2_2") (pintype "passive"))
      (node (ref "R25B") (pin "2") (pinfunction "2_2") (pintype "passive"))
    )
    (net (code "82") (name "P3.3V_DELAYED") (class "Default")
      (node (ref "P10B") (pin "2") (pinfunction "2_2") (pintype "passive"))
      (node (ref "P_EXT") (pin "1") (pinfunction "1_1") (pintype "passive"))
      (node (ref "P_SATA") (pin "1") (pinfunction "1_1") (pintype "passive"))
      (node (ref "R13B") (pin "2") (pinfunction "2_2") (pintype "passive"))
      (node (ref "R14B") (pin "2") (pinfunction "2_2") (pintype "passive"))
      (node (ref "R15B") (pin "2") (pinfunction "2_2") (pintype "passive"))
      (node (ref "R16B") (pin "2") (pinfunction "2_2") (pintype "passive"))
      (node (ref "R22B") (pin "2") (pinfunction "2_2") (pintype "passive"))
      (node (ref "R35B") (pin "1") (pinfunction "1_1") (pintype "passive"))
      (node (ref "R36B") (pin "1") (pinfunction "1_1") (pintype "passive"))
      (node (ref "R39B") (pin "1") (pinfunction "1_1") (pintype "passive"))
      (node (ref "R41B") (pin "1") (pinfunction "1_1") (pintype "passive"))
      (node (ref "R43B") (pin "1") (pinfunction "1_1") (pintype "passive"))
    )
    (net (code "83") (name "unconnected-(U100A-EIM_D31-PadH21)") (class "Default")
      (node (ref "U100") (pin "H21") (pinfunction "EIM_D31_H21") (pintype "bidirectional"))
    )
    (net (code "84") (name "unconnected-(U100A-EIM_EB0-PadK21)") (class "Default")
      (node (ref "U100") (pin "K21") (pinfunction "EIM_EB0_K21") (pintype "bidirectional"))
    )
    (net (code "85") (name "unconnected-(U100A-EIM_EB1-PadK23)") (class "Default")
      (node (ref "U100") (pin "K23") (pinfunction "EIM_EB1_K23") (pintype "bidirectional"))
    )
    (net (code "86") (name "unconnected-(U100A-EIM_EB3-PadF23)") (class "Default")
      (node (ref "U100") (pin "F23") (pinfunction "EIM_EB3_F23") (pintype "bidirectional"))
    )
  )
)
